# CN-Cape003_ohne_HDMI.net
KiCad netlist of a schematic drawn in EAGLE
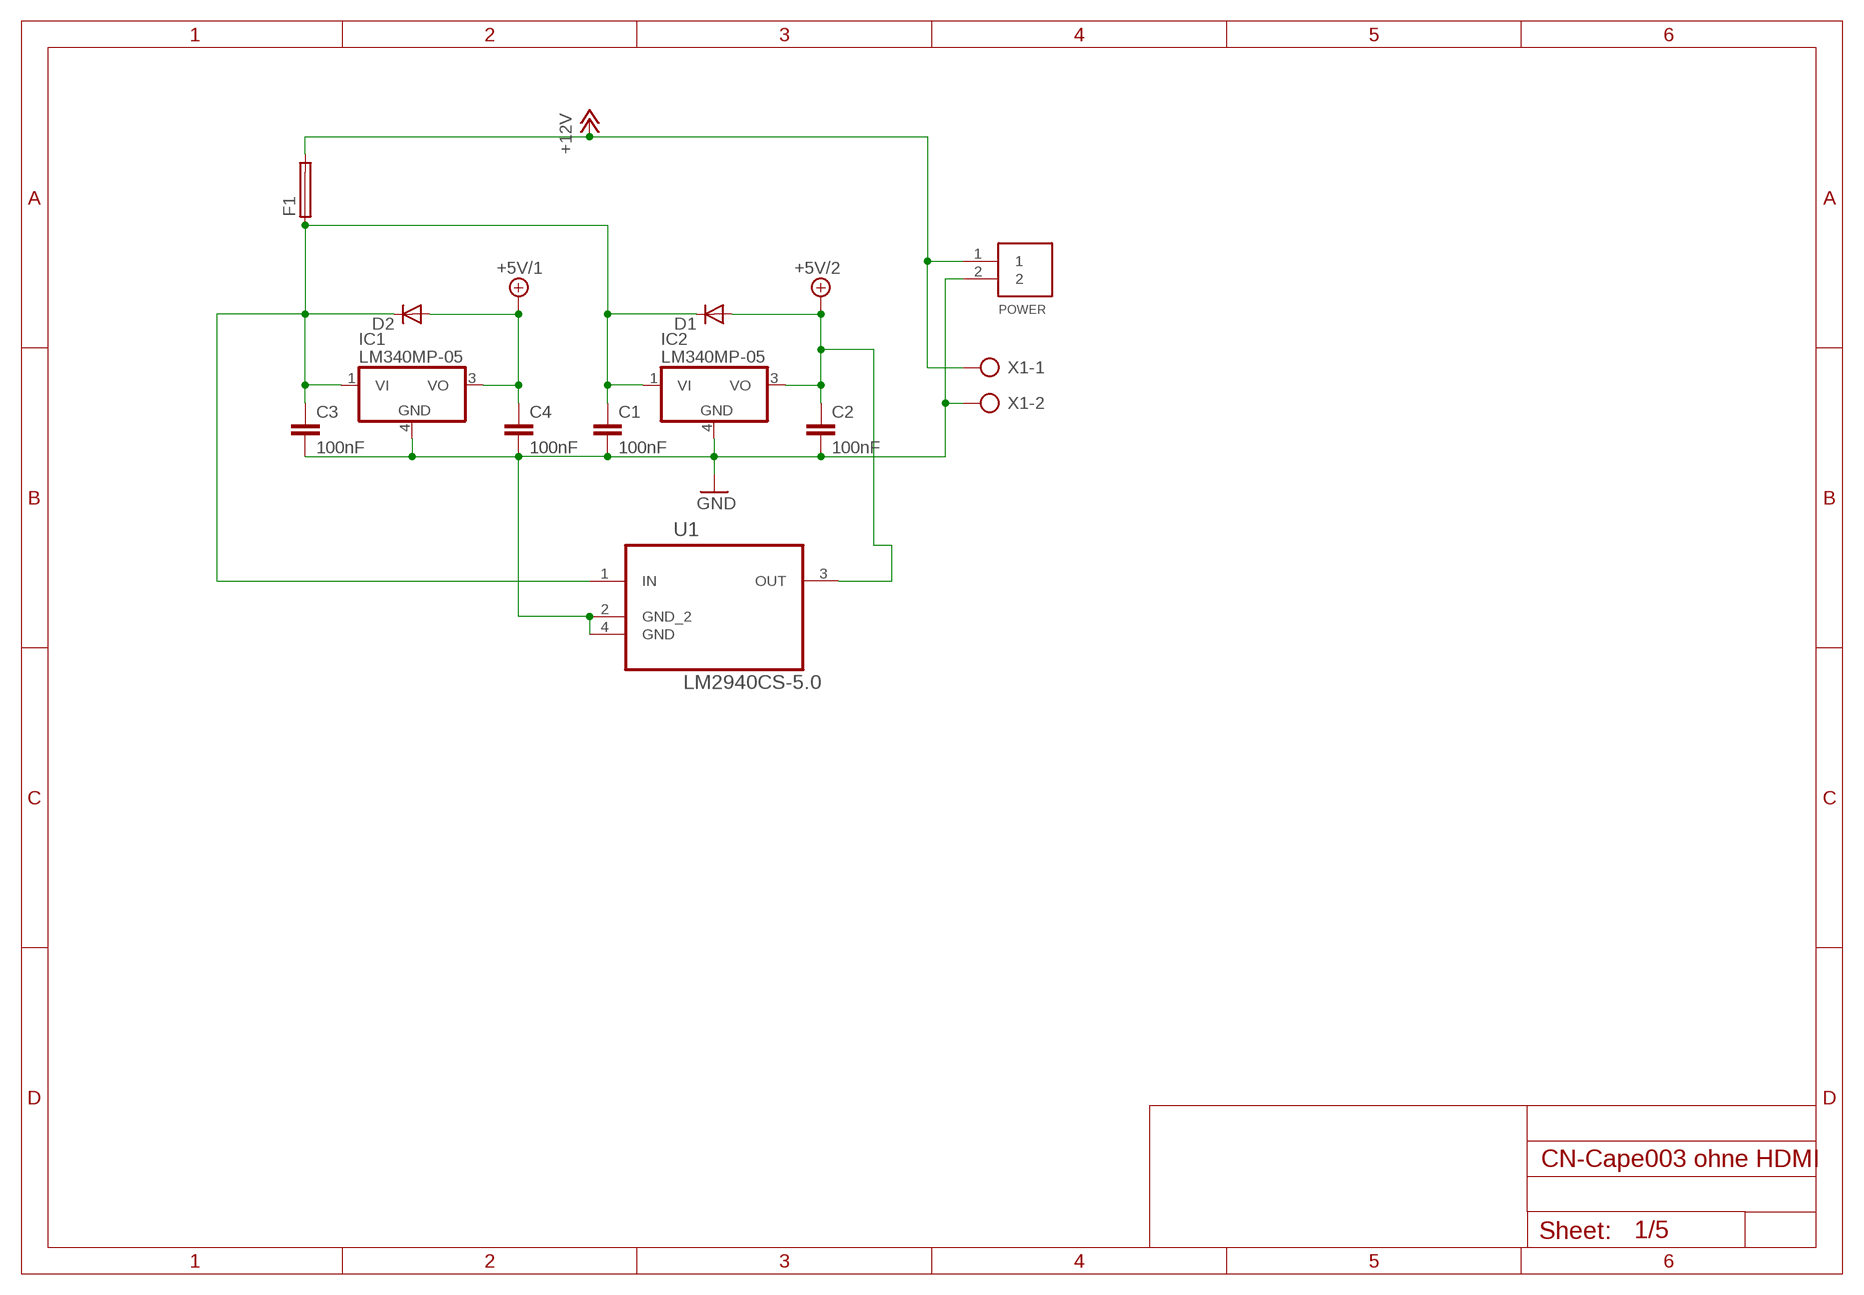
[diagram p0: schematic, sheet 1]
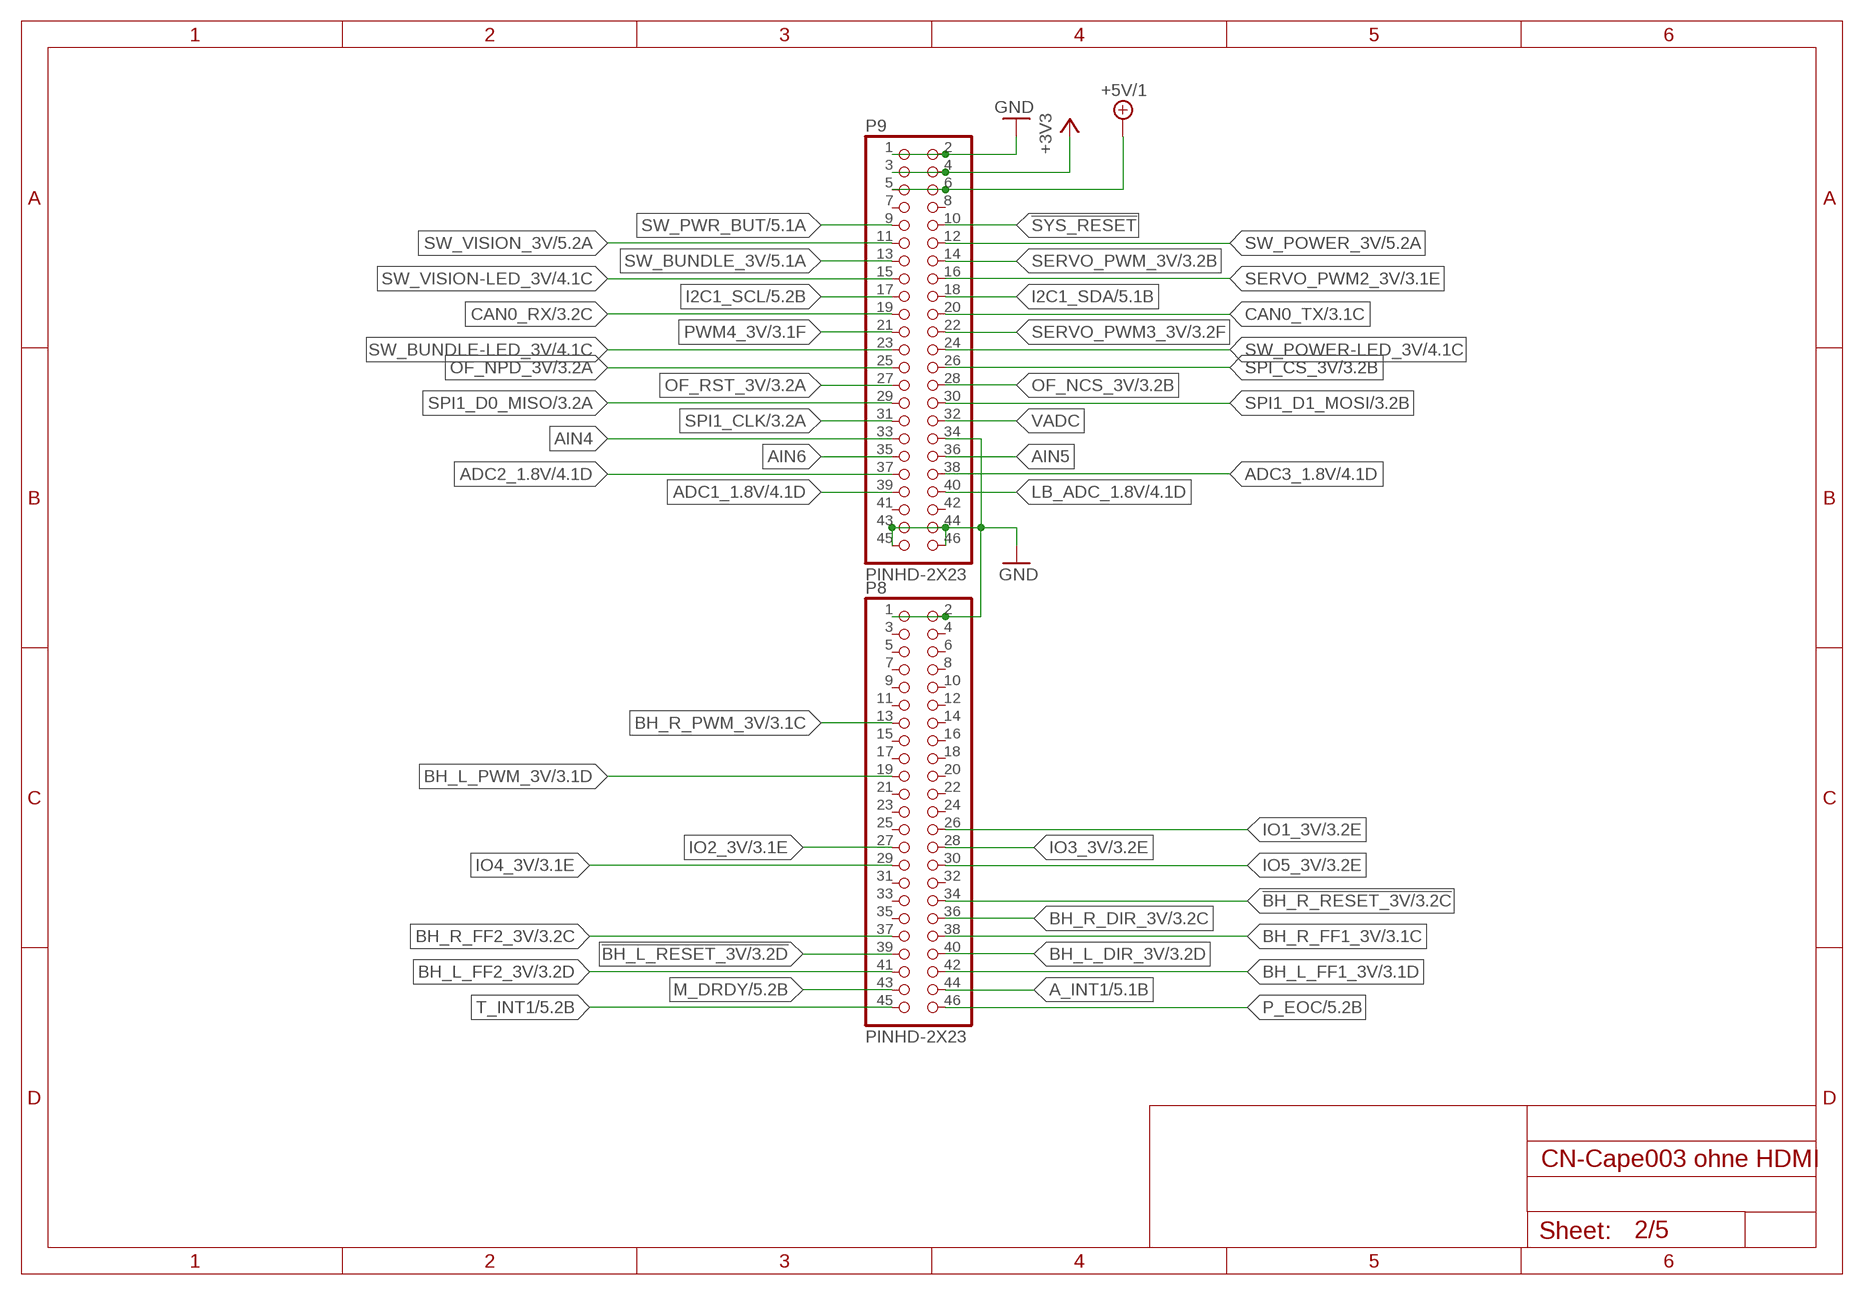
[diagram p1: schematic, sheet 2]
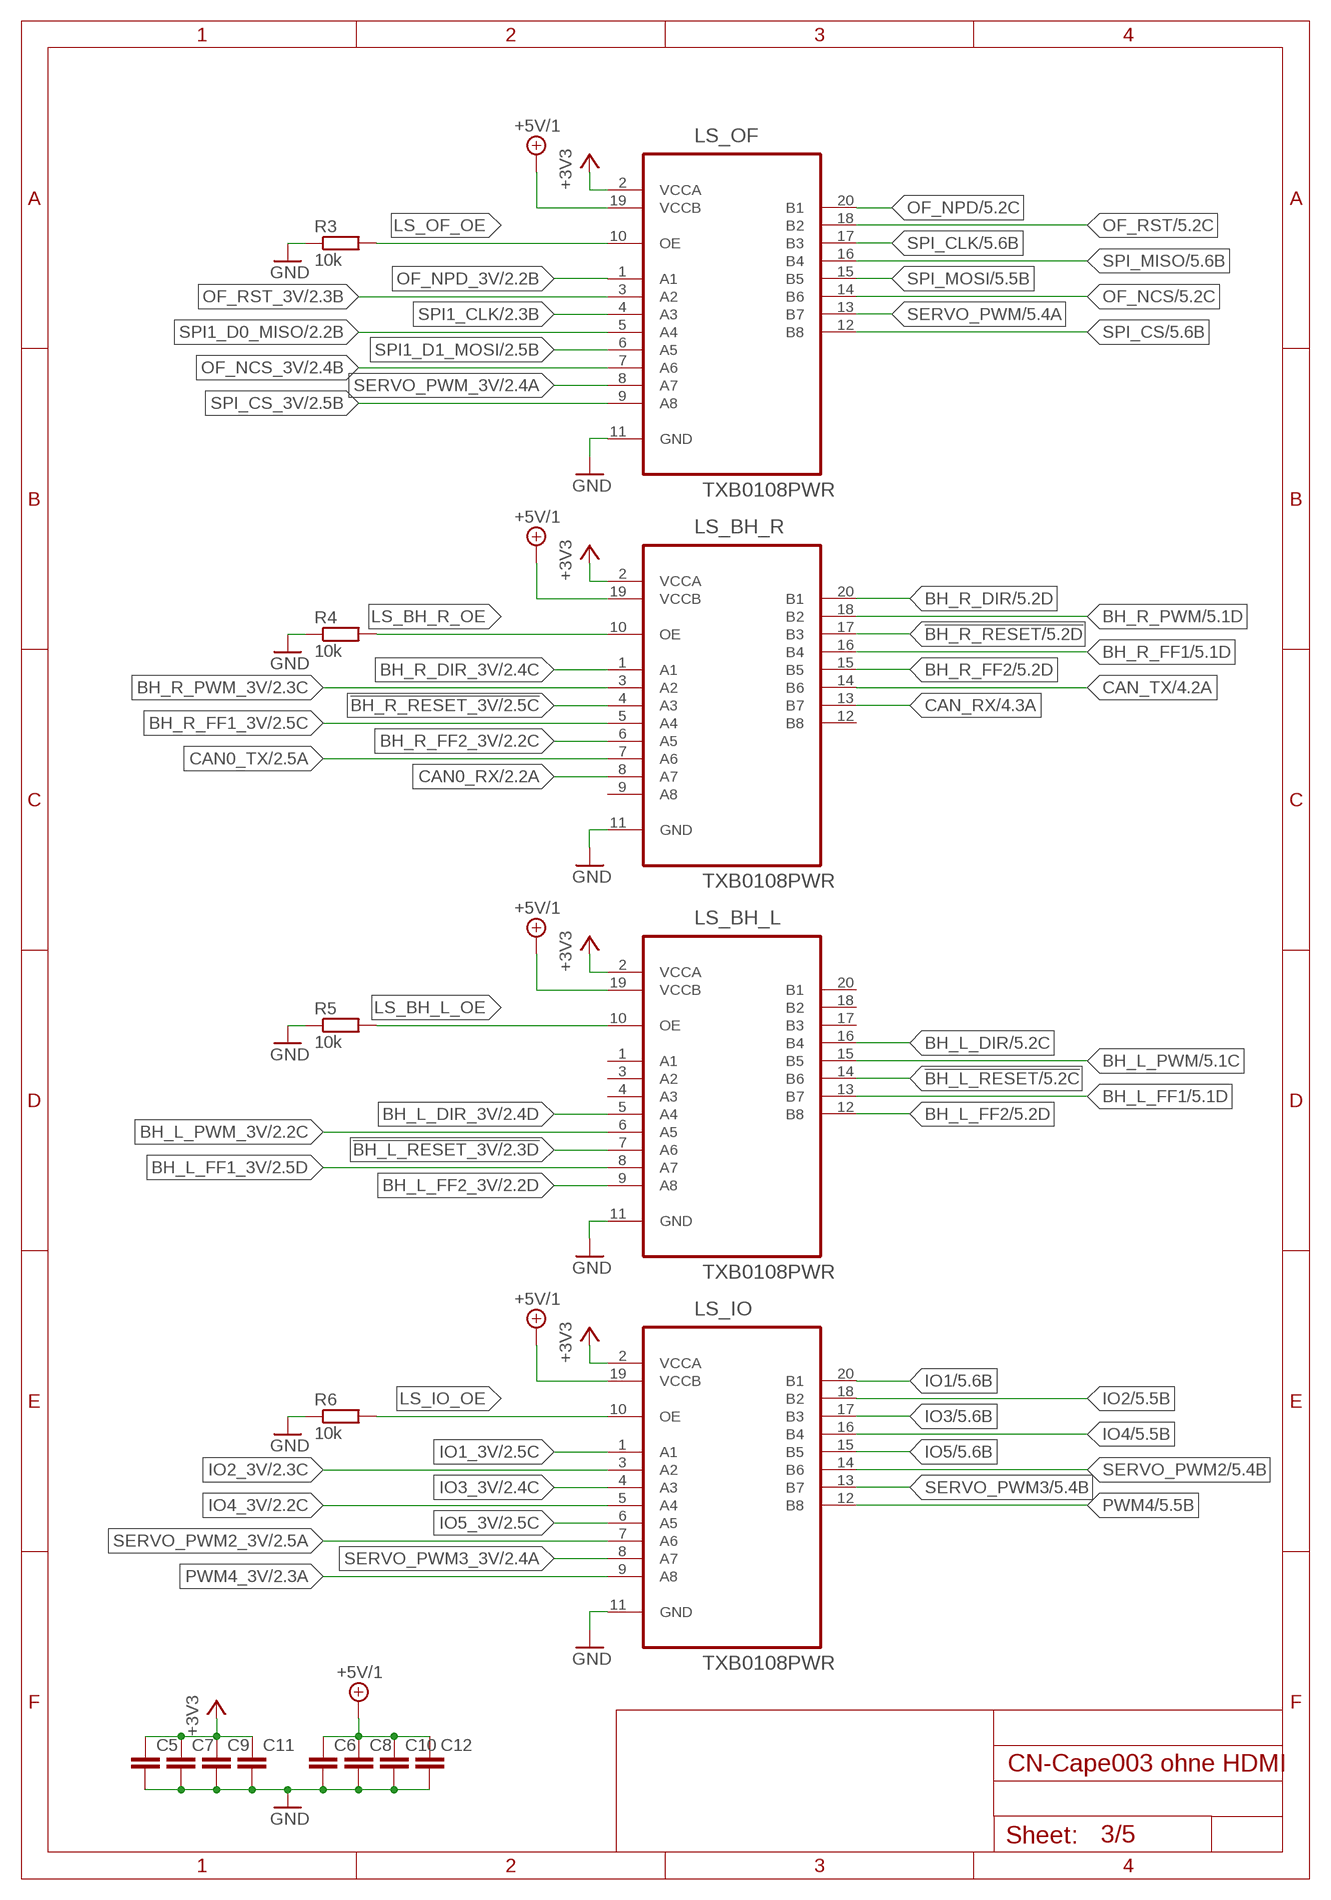
[diagram p2: schematic, sheet 3]
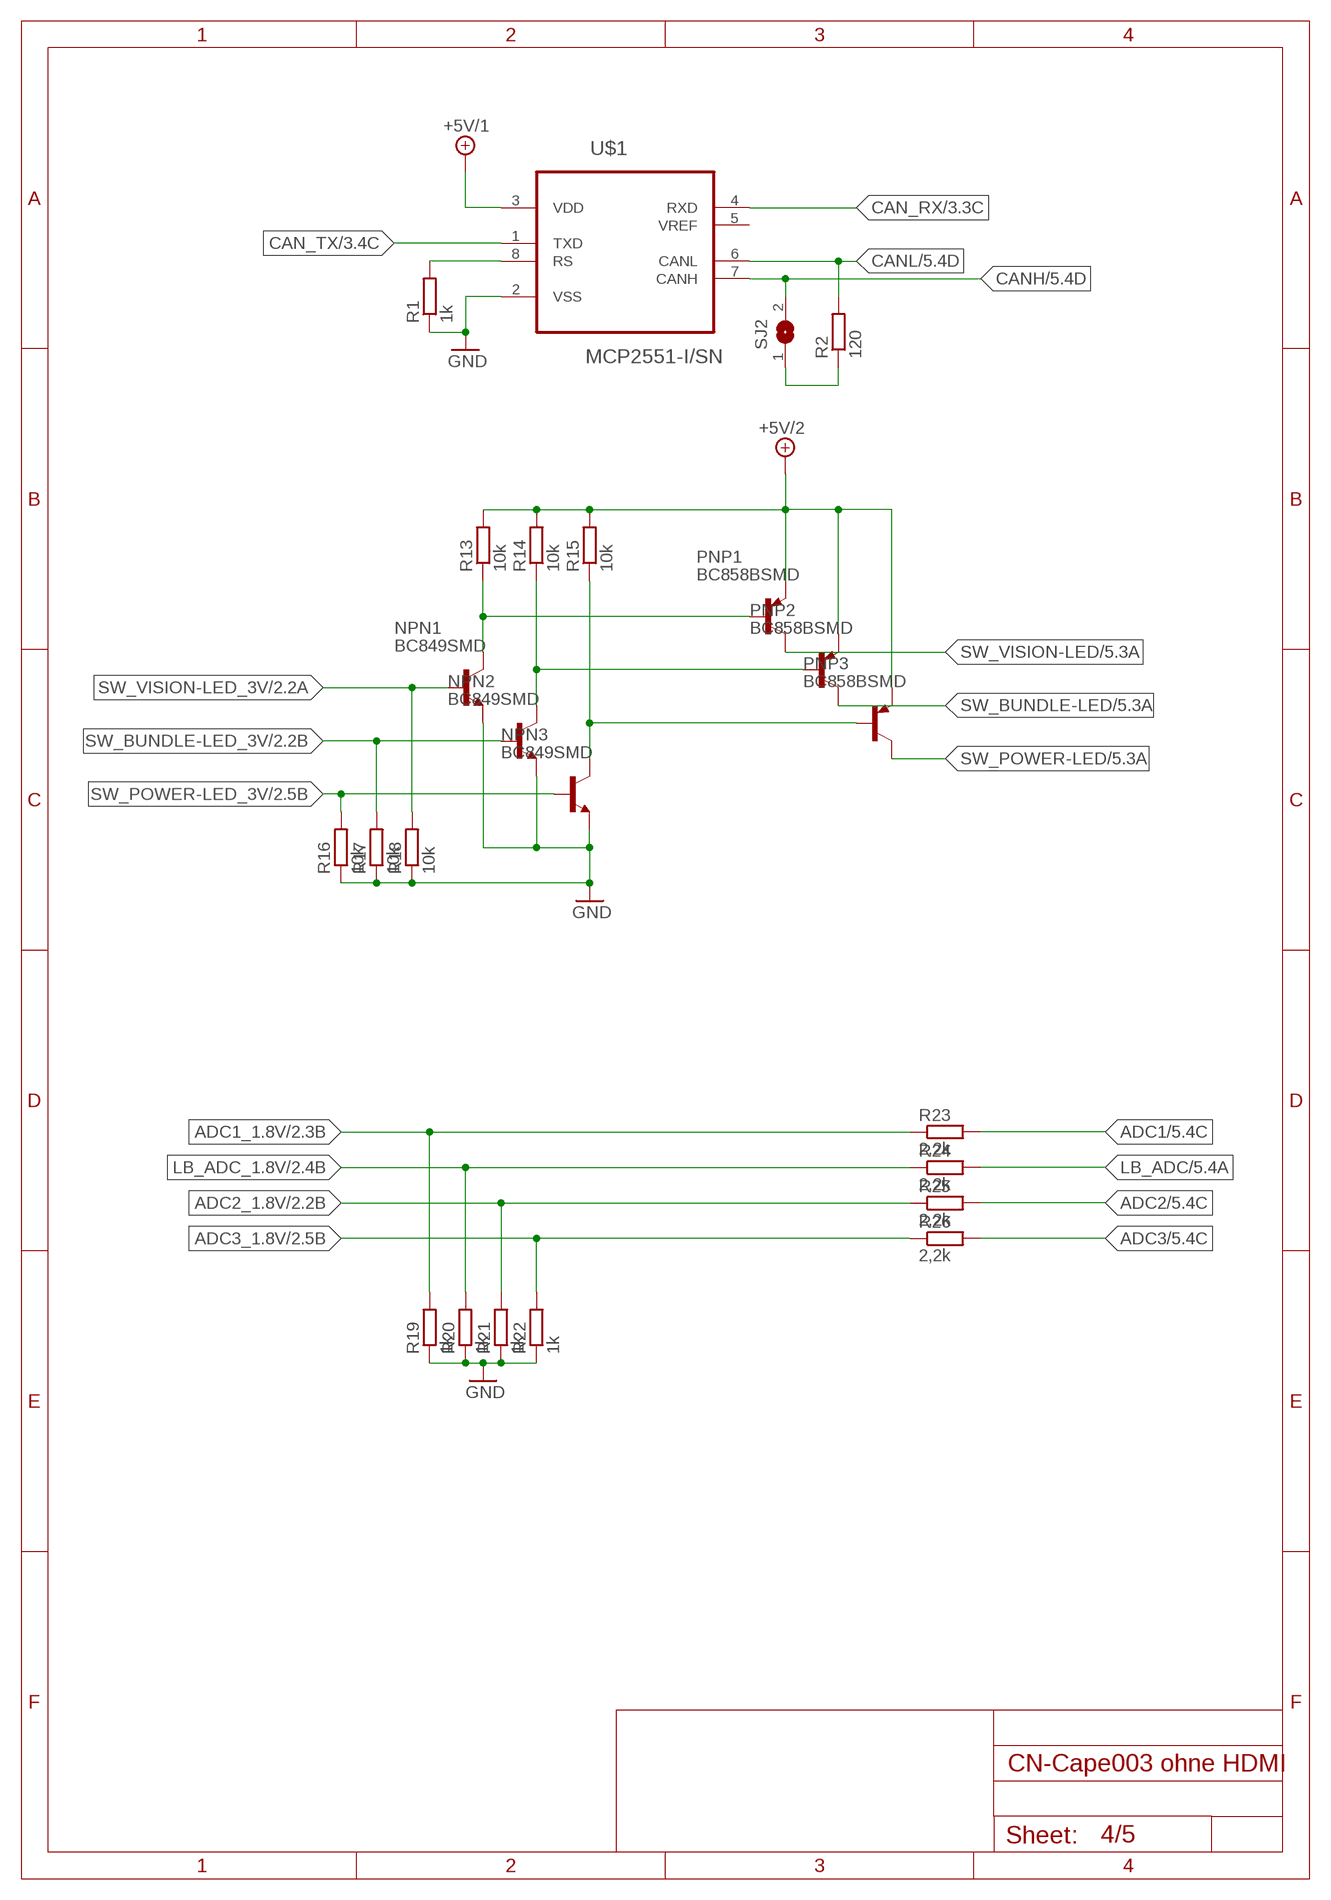
[diagram p3: schematic, sheet 4]
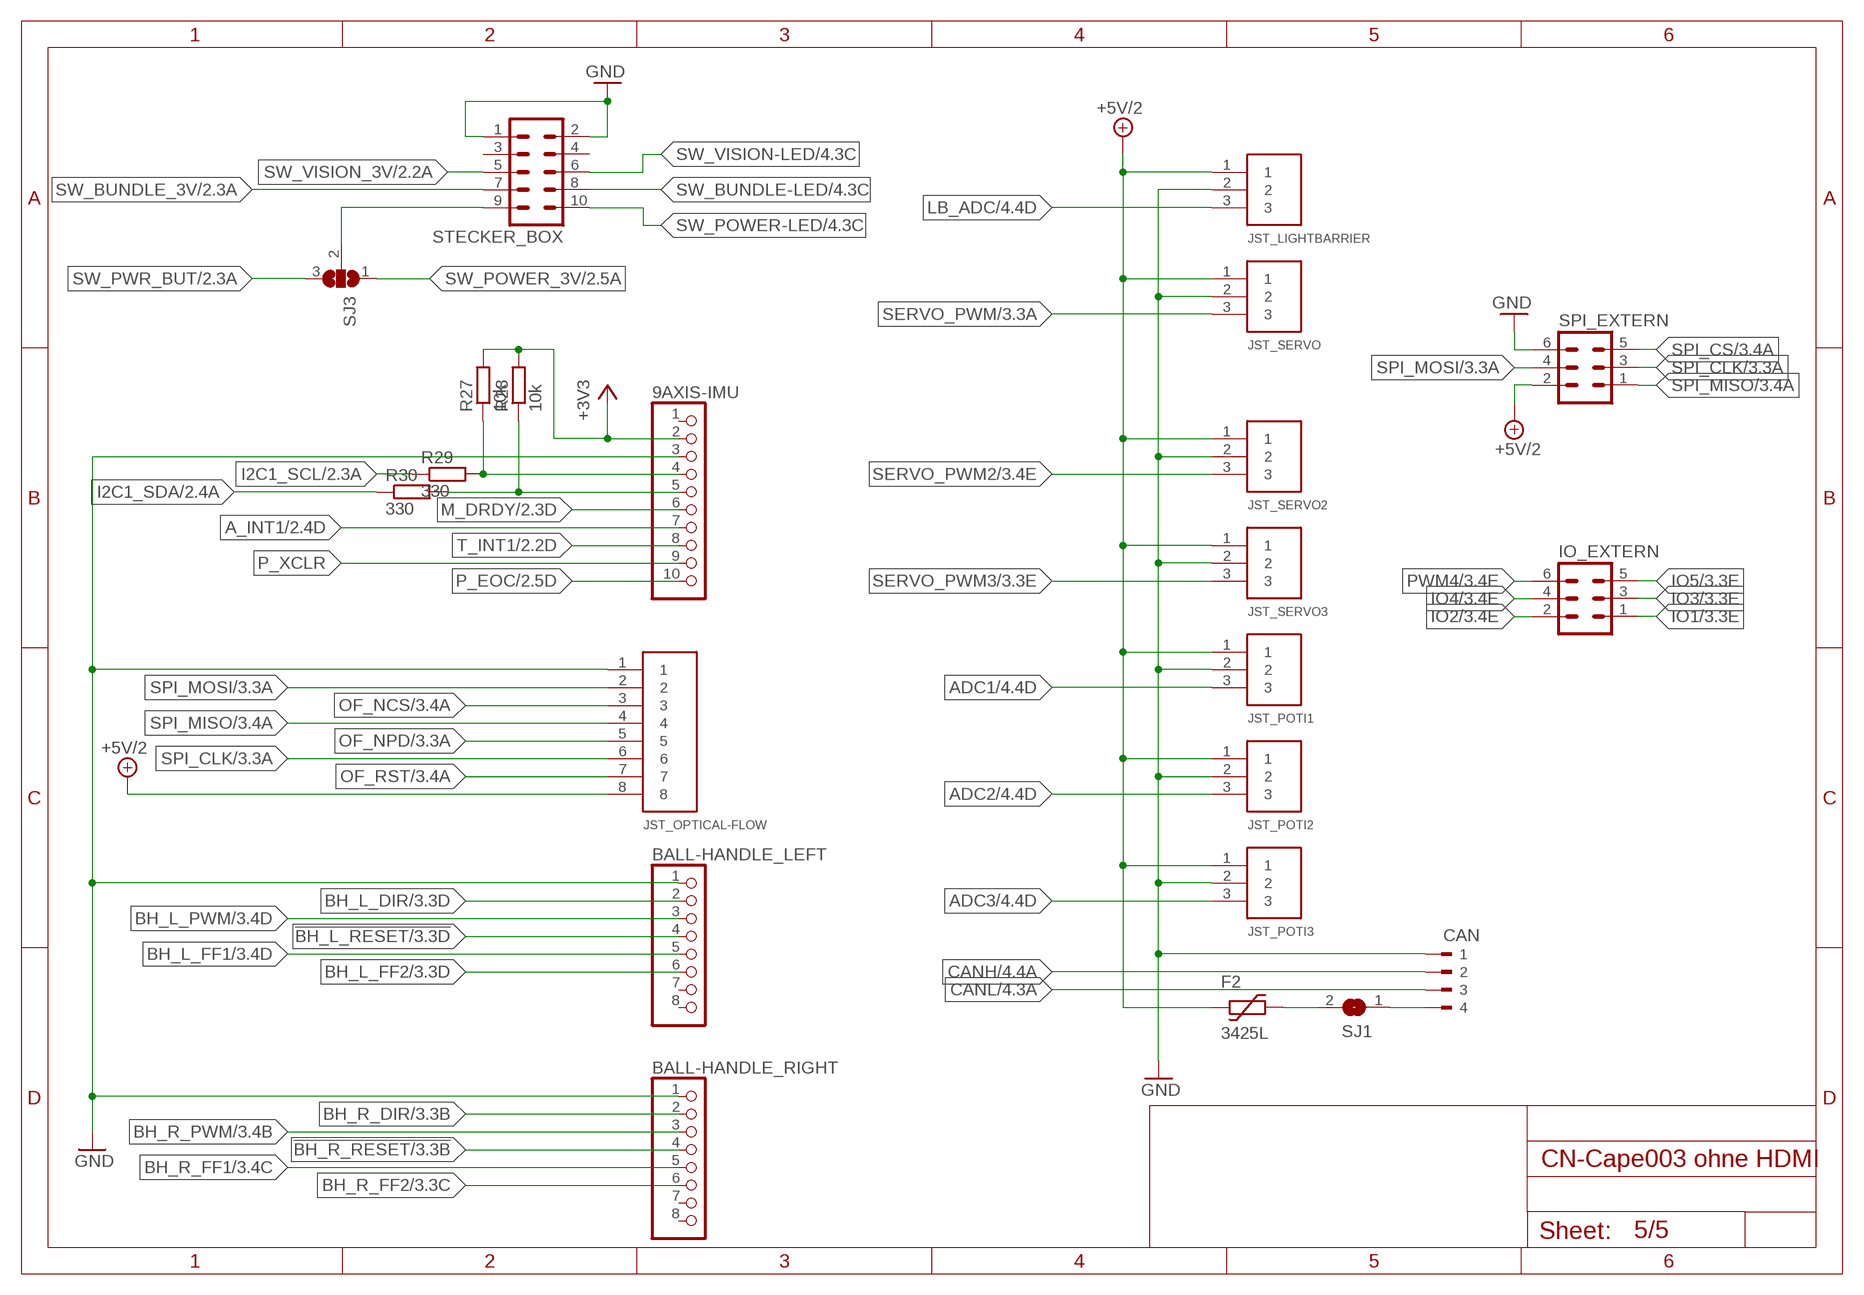
[diagram p4: schematic, sheet 5]

(export (version "E")
  (design (tool "Eeschema 10.0.6"))
  (components
    (comp (ref "C1")
      (value "100nF")
      (footprint "eagle-import:C0805")
      (libsource (lib "eagle-import") (part "C-EUC0805"))
    )
    (comp (ref "C2")
      (value "100nF")
      (footprint "eagle-import:C0805")
      (libsource (lib "eagle-import") (part "C-EUC0805"))
    )
    (comp (ref "C3")
      (value "100nF")
      (footprint "eagle-import:C0805")
      (libsource (lib "eagle-import") (part "C-EUC0805"))
    )
    (comp (ref "C4")
      (value "100nF")
      (footprint "eagle-import:C0805")
      (libsource (lib "eagle-import") (part "C-EUC0805"))
    )
    (comp (ref "D1")
      (value "DIODE-SOD123")
      (footprint "eagle-import:SOD123")
      (libsource (lib "eagle-import") (part "DIODE-SOD123"))
    )
    (comp (ref "D2")
      (value "DIODE-SOD123")
      (footprint "eagle-import:SOD123")
      (libsource (lib "eagle-import") (part "DIODE-SOD123"))
    )
    (comp (ref "F1")
      (value "SH22,5")
      (footprint "eagle-import:SH22,5")
      (libsource (lib "eagle-import") (part "SH22,5"))
    )
    (comp (ref "IC1")
      (value "LM340MP-05")
      (footprint "eagle-import:SOT223")
      (libsource (lib "eagle-import") (part "LM340?-MP05"))
    )
    (comp (ref "IC2")
      (value "LM340MP-05")
      (footprint "eagle-import:SOT223")
      (libsource (lib "eagle-import") (part "LM340?-MP05"))
    )
    (comp (ref "POWER")
      (value "S2PIN")
      (footprint "eagle-import:S2B-EH")
      (libsource (lib "eagle-import") (part "S2PIN"))
    )
    (comp (ref "U1")
      (value "LM2940CS-5.0")
      (footprint "eagle-import:TO254P1435X464-4N")
      (libsource (lib "eagle-import") (part "LM2940CS-5.0"))
    )
    (comp (ref "X1")
      (value "AK500/2-H")
      (footprint "eagle-import:AK500_2-H")
      (libsource (lib "eagle-import") (part "AK500/2-H"))
    )
    (comp (ref "NPN1")
      (value "BC849SMD")
      (footprint "eagle-import:SOT23-BEC")
      (libsource (lib "eagle-import") (part "BC849SMD"))
    )
    (comp (ref "NPN2")
      (value "BC849SMD")
      (footprint "eagle-import:SOT23-BEC")
      (libsource (lib "eagle-import") (part "BC849SMD"))
    )
    (comp (ref "NPN3")
      (value "BC849SMD")
      (footprint "eagle-import:SOT23-BEC")
      (libsource (lib "eagle-import") (part "BC849SMD"))
    )
    (comp (ref "PNP1")
      (value "BC858BSMD")
      (footprint "eagle-import:SOT23-BEC")
      (libsource (lib "eagle-import") (part "BC858SMDB"))
    )
    (comp (ref "PNP2")
      (value "BC858BSMD")
      (footprint "eagle-import:SOT23-BEC")
      (libsource (lib "eagle-import") (part "BC858SMDB"))
    )
    (comp (ref "PNP3")
      (value "BC858BSMD")
      (footprint "eagle-import:SOT23-BEC")
      (libsource (lib "eagle-import") (part "BC858SMDB"))
    )
    (comp (ref "R1")
      (value "1k")
      (footprint "eagle-import:R0603")
      (libsource (lib "eagle-import") (part "R-EU_R0603"))
    )
    (comp (ref "R2")
      (value "120")
      (footprint "eagle-import:R0603")
      (libsource (lib "eagle-import") (part "R-EU_R0603"))
    )
    (comp (ref "R13")
      (value "10k")
      (footprint "eagle-import:R0603")
      (libsource (lib "eagle-import") (part "R-EU_R0603"))
    )
    (comp (ref "R14")
      (value "10k")
      (footprint "eagle-import:R0603")
      (libsource (lib "eagle-import") (part "R-EU_R0603"))
    )
    (comp (ref "R15")
      (value "10k")
      (footprint "eagle-import:R0603")
      (libsource (lib "eagle-import") (part "R-EU_R0603"))
    )
    (comp (ref "R16")
      (value "10k")
      (footprint "eagle-import:R0603")
      (libsource (lib "eagle-import") (part "R-EU_R0603"))
    )
    (comp (ref "R17")
      (value "10k")
      (footprint "eagle-import:R0603")
      (libsource (lib "eagle-import") (part "R-EU_R0603"))
    )
    (comp (ref "R18")
      (value "10k")
      (footprint "eagle-import:R0603")
      (libsource (lib "eagle-import") (part "R-EU_R0603"))
    )
    (comp (ref "R19")
      (value "1k")
      (footprint "eagle-import:R0603")
      (libsource (lib "eagle-import") (part "R-EU_R0603"))
    )
    (comp (ref "R20")
      (value "1k")
      (footprint "eagle-import:R0603")
      (libsource (lib "eagle-import") (part "R-EU_R0603"))
    )
    (comp (ref "R21")
      (value "1k")
      (footprint "eagle-import:R0603")
      (libsource (lib "eagle-import") (part "R-EU_R0603"))
    )
    (comp (ref "R22")
      (value "1k")
      (footprint "eagle-import:R0603")
      (libsource (lib "eagle-import") (part "R-EU_R0603"))
    )
    (comp (ref "R23")
      (value "2,2k")
      (footprint "eagle-import:R0603")
      (libsource (lib "eagle-import") (part "R-EU_R0603"))
    )
    (comp (ref "R24")
      (value "2,2k")
      (footprint "eagle-import:R0603")
      (libsource (lib "eagle-import") (part "R-EU_R0603"))
    )
    (comp (ref "R25")
      (value "2,2k")
      (footprint "eagle-import:R0603")
      (libsource (lib "eagle-import") (part "R-EU_R0603"))
    )
    (comp (ref "R26")
      (value "2,2k")
      (footprint "eagle-import:R0603")
      (libsource (lib "eagle-import") (part "R-EU_R0603"))
    )
    (comp (ref "SJ2") (value "SJ") (footprint "eagle-import:SJ") (libsource (lib "eagle-import") (part "SJ")))
    (comp (ref "U$1")
      (value "MCP2551-I/SN")
      (footprint "eagle-import:SOIC127P600X175-8N")
      (libsource (lib "eagle-import") (part "MCP2551-I/SN"))
    )
    (comp (ref "C5")
      (value "C-EUC0805")
      (footprint "eagle-import:C0805")
      (libsource (lib "eagle-import") (part "C-EUC0805"))
    )
    (comp (ref "C6")
      (value "C-EUC0805")
      (footprint "eagle-import:C0805")
      (libsource (lib "eagle-import") (part "C-EUC0805"))
    )
    (comp (ref "C7")
      (value "C-EUC0805")
      (footprint "eagle-import:C0805")
      (libsource (lib "eagle-import") (part "C-EUC0805"))
    )
    (comp (ref "C8")
      (value "C-EUC0805")
      (footprint "eagle-import:C0805")
      (libsource (lib "eagle-import") (part "C-EUC0805"))
    )
    (comp (ref "C9")
      (value "C-EUC0805")
      (footprint "eagle-import:C0805")
      (libsource (lib "eagle-import") (part "C-EUC0805"))
    )
    (comp (ref "C10")
      (value "C-EUC0805")
      (footprint "eagle-import:C0805")
      (libsource (lib "eagle-import") (part "C-EUC0805"))
    )
    (comp (ref "C11")
      (value "C-EUC0805")
      (footprint "eagle-import:C0805")
      (libsource (lib "eagle-import") (part "C-EUC0805"))
    )
    (comp (ref "C12")
      (value "C-EUC0805")
      (footprint "eagle-import:C0805")
      (libsource (lib "eagle-import") (part "C-EUC0805"))
    )
    (comp (ref "LS_BH_L")
      (value "TXB0108PWR")
      (footprint "eagle-import:SOP65P640X120-20N")
      (libsource (lib "eagle-import") (part "TXB0108PWR"))
    )
    (comp (ref "LS_BH_R")
      (value "TXB0108PWR")
      (footprint "eagle-import:SOP65P640X120-20N")
      (libsource (lib "eagle-import") (part "TXB0108PWR"))
    )
    (comp (ref "LS_IO")
      (value "TXB0108PWR")
      (footprint "eagle-import:SOP65P640X120-20N")
      (libsource (lib "eagle-import") (part "TXB0108PWR"))
    )
    (comp (ref "LS_OF")
      (value "TXB0108PWR")
      (footprint "eagle-import:SOP65P640X120-20N")
      (libsource (lib "eagle-import") (part "TXB0108PWR"))
    )
    (comp (ref "R3")
      (value "10k")
      (footprint "eagle-import:R0603")
      (libsource (lib "eagle-import") (part "R-EU_R0603"))
    )
    (comp (ref "R4")
      (value "10k")
      (footprint "eagle-import:R0603")
      (libsource (lib "eagle-import") (part "R-EU_R0603"))
    )
    (comp (ref "R5")
      (value "10k")
      (footprint "eagle-import:R0603")
      (libsource (lib "eagle-import") (part "R-EU_R0603"))
    )
    (comp (ref "R6")
      (value "10k")
      (footprint "eagle-import:R0603")
      (libsource (lib "eagle-import") (part "R-EU_R0603"))
    )
    (comp (ref "P8")
      (value "PINHD-2X23")
      (footprint "eagle-import:2X23")
      (libsource (lib "eagle-import") (part "PINHD-2X23"))
    )
    (comp (ref "P9")
      (value "PINHD-2X23")
      (footprint "eagle-import:2X23")
      (libsource (lib "eagle-import") (part "PINHD-2X23"))
    )
    (comp (ref "9AXIS-IMU")
      (value "PINHD-1X10")
      (footprint "eagle-import:1X10")
      (libsource (lib "eagle-import") (part "PINHD-1X10"))
    )
    (comp (ref "BALL-HANDLE_LEFT")
      (value "PINHD-1X8")
      (footprint "eagle-import:1X08")
      (libsource (lib "eagle-import") (part "PINHD-1X8"))
    )
    (comp (ref "BALL-HANDLE_RIGHT")
      (value "PINHD-1X8")
      (footprint "eagle-import:1X08")
      (libsource (lib "eagle-import") (part "PINHD-1X8"))
    )
    (comp (ref "CAN")
      (value "90-4")
      (footprint "eagle-import:90-4")
      (libsource (lib "eagle-import") (part "90-4"))
    )
    (comp (ref "F2")
      (value "3425L")
      (footprint "eagle-import:3425L")
      (libsource (lib "eagle-import") (part "3425L"))
    )
    (comp (ref "IO_EXTERN")
      (value "ML6")
      (footprint "eagle-import:ML6")
      (libsource (lib "eagle-import") (part "ML6"))
    )
    (comp (ref "JST_LIGHTBARRIER")
      (value "S3PIN")
      (footprint "eagle-import:S3B-EH")
      (libsource (lib "eagle-import") (part "S3PIN"))
    )
    (comp (ref "JST_OPTICAL-FLOW")
      (value "S8PIN")
      (footprint "eagle-import:S8B-EH")
      (libsource (lib "eagle-import") (part "S8PIN"))
    )
    (comp (ref "JST_POTI1")
      (value "3PIN")
      (footprint "eagle-import:B3B-EH")
      (libsource (lib "eagle-import") (part "3PIN"))
    )
    (comp (ref "JST_POTI2")
      (value "3PIN")
      (footprint "eagle-import:B3B-EH")
      (libsource (lib "eagle-import") (part "3PIN"))
    )
    (comp (ref "JST_POTI3")
      (value "3PIN")
      (footprint "eagle-import:B3B-EH")
      (libsource (lib "eagle-import") (part "3PIN"))
    )
    (comp (ref "JST_SERVO")
      (value "S3PIN")
      (footprint "eagle-import:S3B-EH")
      (libsource (lib "eagle-import") (part "S3PIN"))
    )
    (comp (ref "JST_SERVO2")
      (value "3PIN")
      (footprint "eagle-import:B3B-EH")
      (libsource (lib "eagle-import") (part "3PIN"))
    )
    (comp (ref "JST_SERVO3")
      (value "3PIN")
      (footprint "eagle-import:B3B-EH")
      (libsource (lib "eagle-import") (part "3PIN"))
    )
    (comp (ref "R27")
      (value "10k")
      (footprint "eagle-import:R0603")
      (libsource (lib "eagle-import") (part "R-EU_R0603"))
    )
    (comp (ref "R28")
      (value "10k")
      (footprint "eagle-import:R0603")
      (libsource (lib "eagle-import") (part "R-EU_R0603"))
    )
    (comp (ref "R29")
      (value "330")
      (footprint "eagle-import:R0603")
      (libsource (lib "eagle-import") (part "R-EU_R0603"))
    )
    (comp (ref "R30")
      (value "330")
      (footprint "eagle-import:R0603")
      (libsource (lib "eagle-import") (part "R-EU_R0603"))
    )
    (comp (ref "SJ1") (value "SJ") (footprint "eagle-import:SJ") (libsource (lib "eagle-import") (part "SJ")))
    (comp (ref "SJ3")
      (value "SJ2W")
      (footprint "eagle-import:SJ_2")
      (libsource (lib "eagle-import") (part "SJ2W"))
    )
    (comp (ref "SPI_EXTERN")
      (value "ML6")
      (footprint "eagle-import:ML6")
      (libsource (lib "eagle-import") (part "ML6"))
    )
    (comp (ref "STECKER_BOX")
      (value "ML10")
      (footprint "eagle-import:ML10")
      (libsource (lib "eagle-import") (part "ML10"))
    )
  )
  (nets
    (net (code "1") (name "+3V3") (class "Default")
      (node (ref "9AXIS-IMU") (pin "2") (pinfunction "2_2") (pintype "passive"))
      (node (ref "C11") (pin "1") (pinfunction "1_1") (pintype "passive"))
      (node (ref "C5") (pin "1") (pinfunction "1_1") (pintype "passive"))
      (node (ref "C7") (pin "1") (pinfunction "1_1") (pintype "passive"))
      (node (ref "C9") (pin "1") (pinfunction "1_1") (pintype "passive"))
      (node (ref "LS_BH_L") (pin "2") (pinfunction "VCCA_2") (pintype "power_in"))
      (node (ref "LS_BH_R") (pin "2") (pinfunction "VCCA_2") (pintype "power_in"))
      (node (ref "LS_IO") (pin "2") (pinfunction "VCCA_2") (pintype "power_in"))
      (node (ref "LS_OF") (pin "2") (pinfunction "VCCA_2") (pintype "power_in"))
      (node (ref "P9") (pin "3") (pinfunction "3_3") (pintype "passive"))
      (node (ref "P9") (pin "4") (pinfunction "4_4") (pintype "passive"))
      (node (ref "R27") (pin "2") (pinfunction "2_2") (pintype "passive"))
      (node (ref "R28") (pin "2") (pinfunction "2_2") (pintype "passive"))
    )
    (net (code "2") (name "+5V{slash}1") (class "Default")
      (node (ref "C10") (pin "1") (pinfunction "1_1") (pintype "passive"))
      (node (ref "C12") (pin "1") (pinfunction "1_1") (pintype "passive"))
      (node (ref "C4") (pin "1") (pinfunction "1_1") (pintype "passive"))
      (node (ref "C6") (pin "1") (pinfunction "1_1") (pintype "passive"))
      (node (ref "C8") (pin "1") (pinfunction "1_1") (pintype "passive"))
      (node (ref "D2") (pin "A") (pinfunction "A_A") (pintype "passive"))
      (node (ref "IC1") (pin "3") (pinfunction "VO_3") (pintype "passive"))
      (node (ref "LS_BH_L") (pin "19") (pinfunction "VCCB_19") (pintype "power_in"))
      (node (ref "LS_BH_R") (pin "19") (pinfunction "VCCB_19") (pintype "power_in"))
      (node (ref "LS_IO") (pin "19") (pinfunction "VCCB_19") (pintype "power_in"))
      (node (ref "LS_OF") (pin "19") (pinfunction "VCCB_19") (pintype "power_in"))
      (node (ref "P9") (pin "5") (pinfunction "5_5") (pintype "passive"))
      (node (ref "P9") (pin "6") (pinfunction "6_6") (pintype "passive"))
      (node (ref "U$1") (pin "3") (pinfunction "VDD_3") (pintype "power_in"))
    )
    (net (code "3") (name "+5V{slash}2") (class "Default")
      (node (ref "C2") (pin "1") (pinfunction "1_1") (pintype "passive"))
      (node (ref "D1") (pin "A") (pinfunction "A_A") (pintype "passive"))
      (node (ref "F2") (pin "P$1") (pinfunction "1_P$1") (pintype "passive"))
      (node (ref "IC2") (pin "3") (pinfunction "VO_3") (pintype "passive"))
      (node (ref "JST_LIGHTBARRIER") (pin "1") (pinfunction "1_1") (pintype "bidirectional"))
      (node (ref "JST_OPTICAL-FLOW") (pin "8") (pinfunction "8_8") (pintype "bidirectional"))
      (node (ref "JST_POTI1") (pin "1") (pinfunction "1_1") (pintype "bidirectional"))
      (node (ref "JST_POTI2") (pin "1") (pinfunction "1_1") (pintype "bidirectional"))
      (node (ref "JST_POTI3") (pin "1") (pinfunction "1_1") (pintype "bidirectional"))
      (node (ref "JST_SERVO") (pin "1") (pinfunction "1_1") (pintype "bidirectional"))
      (node (ref "JST_SERVO2") (pin "1") (pinfunction "1_1") (pintype "bidirectional"))
      (node (ref "JST_SERVO3") (pin "1") (pinfunction "1_1") (pintype "bidirectional"))
      (node (ref "PNP1") (pin "E") (pinfunction "E_E") (pintype "passive"))
      (node (ref "PNP2") (pin "E") (pinfunction "E_E") (pintype "passive"))
      (node (ref "PNP3") (pin "E") (pinfunction "E_E") (pintype "passive"))
      (node (ref "R13") (pin "2") (pinfunction "2_2") (pintype "passive"))
      (node (ref "R14") (pin "2") (pinfunction "2_2") (pintype "passive"))
      (node (ref "R15") (pin "2") (pinfunction "2_2") (pintype "passive"))
      (node (ref "SPI_EXTERN") (pin "2") (pinfunction "2_2") (pintype "passive"))
      (node (ref "U1") (pin "3") (pinfunction "OUT_3") (pintype "output"))
    )
    (net (code "4") (name "+12V") (class "Default")
      (node (ref "F1") (pin "2") (pinfunction "2_2") (pintype "passive"))
      (node (ref "POWER") (pin "1") (pinfunction "1_1") (pintype "bidirectional"))
      (node (ref "X1") (pin "1") (pinfunction "KL_1") (pintype "passive"))
    )
    (net (code "5") (name "ADC1") (class "Default")
      (node (ref "JST_POTI1") (pin "3") (pinfunction "3_3") (pintype "bidirectional"))
      (node (ref "R23") (pin "2") (pinfunction "2_2") (pintype "passive"))
    )
    (net (code "6") (name "ADC1_1.8V") (class "Default")
      (node (ref "P9") (pin "39") (pinfunction "39_39") (pintype "passive"))
      (node (ref "R19") (pin "2") (pinfunction "2_2") (pintype "passive"))
      (node (ref "R23") (pin "1") (pinfunction "1_1") (pintype "passive"))
    )
    (net (code "7") (name "ADC2") (class "Default")
      (node (ref "JST_POTI2") (pin "3") (pinfunction "3_3") (pintype "bidirectional"))
      (node (ref "R25") (pin "2") (pinfunction "2_2") (pintype "passive"))
    )
    (net (code "8") (name "ADC2_1.8V") (class "Default")
      (node (ref "P9") (pin "37") (pinfunction "37_37") (pintype "passive"))
      (node (ref "R21") (pin "2") (pinfunction "2_2") (pintype "passive"))
      (node (ref "R25") (pin "1") (pinfunction "1_1") (pintype "passive"))
    )
    (net (code "9") (name "ADC3") (class "Default")
      (node (ref "JST_POTI3") (pin "3") (pinfunction "3_3") (pintype "bidirectional"))
      (node (ref "R26") (pin "2") (pinfunction "2_2") (pintype "passive"))
    )
    (net (code "10") (name "ADC3_1.8V") (class "Default")
      (node (ref "P9") (pin "38") (pinfunction "38_38") (pintype "passive"))
      (node (ref "R22") (pin "2") (pinfunction "2_2") (pintype "passive"))
      (node (ref "R26") (pin "1") (pinfunction "1_1") (pintype "passive"))
    )
    (net (code "11") (name "AIN4") (class "Default")
      (node (ref "P9") (pin "33") (pinfunction "33_33") (pintype "passive"))
    )
    (net (code "12") (name "AIN5") (class "Default")
      (node (ref "P9") (pin "36") (pinfunction "36_36") (pintype "passive"))
    )
    (net (code "13") (name "AIN6") (class "Default")
      (node (ref "P9") (pin "35") (pinfunction "35_35") (pintype "passive"))
    )
    (net (code "14") (name "A_INT1") (class "Default")
      (node (ref "9AXIS-IMU") (pin "7") (pinfunction "7_7") (pintype "passive"))
      (node (ref "P8") (pin "44") (pinfunction "44_44") (pintype "passive"))
    )
    (net (code "15") (name "BH_L_DIR") (class "Default")
      (node (ref "BALL-HANDLE_LEFT") (pin "2") (pinfunction "2_2") (pintype "passive"))
      (node (ref "LS_BH_L") (pin "16") (pinfunction "B4_16") (pintype "bidirectional"))
    )
    (net (code "16") (name "BH_L_DIR_3V") (class "Default")
      (node (ref "LS_BH_L") (pin "5") (pinfunction "A4_5") (pintype "bidirectional"))
      (node (ref "P8") (pin "40") (pinfunction "40_40") (pintype "passive"))
    )
    (net (code "17") (name "BH_L_FF1") (class "Default")
      (node (ref "BALL-HANDLE_LEFT") (pin "5") (pinfunction "5_5") (pintype "passive"))
      (node (ref "LS_BH_L") (pin "13") (pinfunction "B7_13") (pintype "bidirectional"))
    )
    (net (code "18") (name "BH_L_FF1_3V") (class "Default")
      (node (ref "LS_BH_L") (pin "8") (pinfunction "A7_8") (pintype "bidirectional"))
      (node (ref "P8") (pin "42") (pinfunction "42_42") (pintype "passive"))
    )
    (net (code "19") (name "BH_L_FF2") (class "Default")
      (node (ref "BALL-HANDLE_LEFT") (pin "6") (pinfunction "6_6") (pintype "passive"))
      (node (ref "LS_BH_L") (pin "12") (pinfunction "B8_12") (pintype "bidirectional"))
    )
    (net (code "20") (name "BH_L_FF2_3V") (class "Default")
      (node (ref "LS_BH_L") (pin "9") (pinfunction "A8_9") (pintype "bidirectional"))
      (node (ref "P8") (pin "41") (pinfunction "41_41") (pintype "passive"))
    )
    (net (code "21") (name "BH_L_PWM") (class "Default")
      (node (ref "BALL-HANDLE_LEFT") (pin "3") (pinfunction "3_3") (pintype "passive"))
      (node (ref "LS_BH_L") (pin "15") (pinfunction "B5_15") (pintype "bidirectional"))
    )
    (net (code "22") (name "BH_L_PWM_3V") (class "Default")
      (node (ref "LS_BH_L") (pin "6") (pinfunction "A5_6") (pintype "bidirectional"))
      (node (ref "P8") (pin "19") (pinfunction "19_19") (pintype "passive"))
    )
    (net (code "23") (name "BH_R_DIR") (class "Default")
      (node (ref "BALL-HANDLE_RIGHT") (pin "2") (pinfunction "2_2") (pintype "passive"))
      (node (ref "LS_BH_R") (pin "20") (pinfunction "B1_20") (pintype "bidirectional"))
    )
    (net (code "24") (name "BH_R_DIR_3V") (class "Default")
      (node (ref "LS_BH_R") (pin "1") (pinfunction "A1_1") (pintype "bidirectional"))
      (node (ref "P8") (pin "36") (pinfunction "36_36") (pintype "passive"))
    )
    (net (code "25") (name "BH_R_FF1") (class "Default")
      (node (ref "BALL-HANDLE_RIGHT") (pin "5") (pinfunction "5_5") (pintype "passive"))
      (node (ref "LS_BH_R") (pin "16") (pinfunction "B4_16") (pintype "bidirectional"))
    )
    (net (code "26") (name "BH_R_FF1_3V") (class "Default")
      (node (ref "LS_BH_R") (pin "5") (pinfunction "A4_5") (pintype "bidirectional"))
      (node (ref "P8") (pin "38") (pinfunction "38_38") (pintype "passive"))
    )
    (net (code "27") (name "BH_R_FF2") (class "Default")
      (node (ref "BALL-HANDLE_RIGHT") (pin "6") (pinfunction "6_6") (pintype "passive"))
      (node (ref "LS_BH_R") (pin "15") (pinfunction "B5_15") (pintype "bidirectional"))
    )
    (net (code "28") (name "BH_R_FF2_3V") (class "Default")
      (node (ref "LS_BH_R") (pin "6") (pinfunction "A5_6") (pintype "bidirectional"))
      (node (ref "P8") (pin "37") (pinfunction "37_37") (pintype "passive"))
    )
    (net (code "29") (name "BH_R_PWM") (class "Default")
      (node (ref "BALL-HANDLE_RIGHT") (pin "3") (pinfunction "3_3") (pintype "passive"))
      (node (ref "LS_BH_R") (pin "18") (pinfunction "B2_18") (pintype "bidirectional"))
    )
    (net (code "30") (name "BH_R_PWM_3V") (class "Default")
      (node (ref "LS_BH_R") (pin "3") (pinfunction "A2_3") (pintype "bidirectional"))
      (node (ref "P8") (pin "13") (pinfunction "13_13") (pintype "passive"))
    )
    (net (code "31") (name "CAN0_RX") (class "Default")
      (node (ref "LS_BH_R") (pin "8") (pinfunction "A7_8") (pintype "bidirectional"))
      (node (ref "P9") (pin "19") (pinfunction "19_19") (pintype "passive"))
    )
    (net (code "32") (name "CAN0_TX") (class "Default")
      (node (ref "LS_BH_R") (pin "7") (pinfunction "A6_7") (pintype "bidirectional"))
      (node (ref "P9") (pin "20") (pinfunction "20_20") (pintype "passive"))
    )
    (net (code "33") (name "CANH") (class "Default")
      (node (ref "CAN") (pin "2") (pinfunction "2_2") (pintype "passive"))
      (node (ref "SJ2") (pin "2") (pinfunction "2_2") (pintype "passive"))
      (node (ref "U$1") (pin "7") (pinfunction "CANH_7") (pintype "bidirectional"))
    )
    (net (code "34") (name "CANL") (class "Default")
      (node (ref "CAN") (pin "3") (pinfunction "3_3") (pintype "passive"))
      (node (ref "R2") (pin "2") (pinfunction "2_2") (pintype "passive"))
      (node (ref "U$1") (pin "6") (pinfunction "CANL_6") (pintype "bidirectional"))
    )
    (net (code "35") (name "CAN_RX") (class "Default")
      (node (ref "LS_BH_R") (pin "13") (pinfunction "B7_13") (pintype "bidirectional"))
      (node (ref "U$1") (pin "4") (pinfunction "RXD_4") (pintype "output"))
    )
    (net (code "36") (name "CAN_TX") (class "Default")
      (node (ref "LS_BH_R") (pin "14") (pinfunction "B6_14") (pintype "bidirectional"))
      (node (ref "U$1") (pin "1") (pinfunction "TXD_1") (pintype "input"))
    )
    (net (code "37") (name "GND") (class "Default")
      (node (ref "9AXIS-IMU") (pin "3") (pinfunction "3_3") (pintype "passive"))
      (node (ref "BALL-HANDLE_LEFT") (pin "1") (pinfunction "1_1") (pintype "passive"))
      (node (ref "BALL-HANDLE_RIGHT") (pin "1") (pinfunction "1_1") (pintype "passive"))
      (node (ref "C1") (pin "2") (pinfunction "2_2") (pintype "passive"))
      (node (ref "C10") (pin "2") (pinfunction "2_2") (pintype "passive"))
      (node (ref "C11") (pin "2") (pinfunction "2_2") (pintype "passive"))
      (node (ref "C12") (pin "2") (pinfunction "2_2") (pintype "passive"))
      (node (ref "C2") (pin "2") (pinfunction "2_2") (pintype "passive"))
      (node (ref "C3") (pin "2") (pinfunction "2_2") (pintype "passive"))
      (node (ref "C4") (pin "2") (pinfunction "2_2") (pintype "passive"))
      (node (ref "C5") (pin "2") (pinfunction "2_2") (pintype "passive"))
      (node (ref "C6") (pin "2") (pinfunction "2_2") (pintype "passive"))
      (node (ref "C7") (pin "2") (pinfunction "2_2") (pintype "passive"))
      (node (ref "C8") (pin "2") (pinfunction "2_2") (pintype "passive"))
      (node (ref "C9") (pin "2") (pinfunction "2_2") (pintype "passive"))
      (node (ref "CAN") (pin "1") (pinfunction "1_1") (pintype "passive"))
      (node (ref "IC1") (pin "4") (pinfunction "GND_4") (pintype "passive"))
      (node (ref "IC2") (pin "4") (pinfunction "GND_4") (pintype "passive"))
      (node (ref "JST_LIGHTBARRIER") (pin "2") (pinfunction "2_2") (pintype "bidirectional"))
      (node (ref "JST_OPTICAL-FLOW") (pin "1") (pinfunction "1_1") (pintype "bidirectional"))
      (node (ref "JST_POTI1") (pin "2") (pinfunction "2_2") (pintype "bidirectional"))
      (node (ref "JST_POTI2") (pin "2") (pinfunction "2_2") (pintype "bidirectional"))
      (node (ref "JST_POTI3") (pin "2") (pinfunction "2_2") (pintype "bidirectional"))
      (node (ref "JST_SERVO") (pin "2") (pinfunction "2_2") (pintype "bidirectional"))
      (node (ref "JST_SERVO2") (pin "2") (pinfunction "2_2") (pintype "bidirectional"))
      (node (ref "JST_SERVO3") (pin "2") (pinfunction "2_2") (pintype "bidirectional"))
      (node (ref "LS_BH_L") (pin "11") (pinfunction "GND_11") (pintype "passive"))
      (node (ref "LS_BH_R") (pin "11") (pinfunction "GND_11") (pintype "passive"))
      (node (ref "LS_IO") (pin "11") (pinfunction "GND_11") (pintype "passive"))
      (node (ref "LS_OF") (pin "11") (pinfunction "GND_11") (pintype "passive"))
      (node (ref "NPN1") (pin "E") (pinfunction "E_E") (pintype "passive"))
      (node (ref "NPN2") (pin "E") (pinfunction "E_E") (pintype "passive"))
      (node (ref "NPN3") (pin "E") (pinfunction "E_E") (pintype "passive"))
      (node (ref "P8") (pin "1") (pinfunction "1_1") (pintype "passive"))
      (node (ref "P8") (pin "2") (pinfunction "2_2") (pintype "passive"))
      (node (ref "P9") (pin "1") (pinfunction "1_1") (pintype "passive"))
      (node (ref "P9") (pin "2") (pinfunction "2_2") (pintype "passive"))
      (node (ref "P9") (pin "34") (pinfunction "34_34") (pintype "passive"))
      (node (ref "P9") (pin "43") (pinfunction "43_43") (pintype "passive"))
      (node (ref "P9") (pin "44") (pinfunction "44_44") (pintype "passive"))
      (node (ref "P9") (pin "45") (pinfunction "45_45") (pintype "passive"))
      (node (ref "P9") (pin "46") (pinfunction "46_46") (pintype "passive"))
      (node (ref "POWER") (pin "2") (pinfunction "2_2") (pintype "bidirectional"))
      (node (ref "R1") (pin "1") (pinfunction "1_1") (pintype "passive"))
      (node (ref "R16") (pin "1") (pinfunction "1_1") (pintype "passive"))
      (node (ref "R17") (pin "1") (pinfunction "1_1") (pintype "passive"))
      (node (ref "R18") (pin "1") (pinfunction "1_1") (pintype "passive"))
      (node (ref "R19") (pin "1") (pinfunction "1_1") (pintype "passive"))
      (node (ref "R20") (pin "1") (pinfunction "1_1") (pintype "passive"))
      (node (ref "R21") (pin "1") (pinfunction "1_1") (pintype "passive"))
      (node (ref "R22") (pin "1") (pinfunction "1_1") (pintype "passive"))
      (node (ref "R3") (pin "1") (pinfunction "1_1") (pintype "passive"))
      (node (ref "R4") (pin "1") (pinfunction "1_1") (pintype "passive"))
      (node (ref "R5") (pin "1") (pinfunction "1_1") (pintype "passive"))
      (node (ref "R6") (pin "1") (pinfunction "1_1") (pintype "passive"))
      (node (ref "SPI_EXTERN") (pin "6") (pinfunction "6_6") (pintype "passive"))
      (node (ref "STECKER_BOX") (pin "1") (pinfunction "1_1") (pintype "passive"))
      (node (ref "STECKER_BOX") (pin "2") (pinfunction "2_2") (pintype "passive"))
      (node (ref "U$1") (pin "2") (pinfunction "VSS_2") (pintype "passive"))
      (node (ref "U1") (pin "2") (pinfunction "GND_2_2") (pintype "passive"))
      (node (ref "U1") (pin "4") (pinfunction "GND_4") (pintype "passive"))
      (node (ref "X1") (pin "2") (pinfunction "KL_2") (pintype "passive"))
    )
    (net (code "38") (name "I2C1_SCL") (class "Default")
      (node (ref "P9") (pin "17") (pinfunction "17_17") (pintype "passive"))
      (node (ref "R29") (pin "1") (pinfunction "1_1") (pintype "passive"))
    )
    (net (code "39") (name "I2C1_SDA") (class "Default")
      (node (ref "P9") (pin "18") (pinfunction "18_18") (pintype "passive"))
      (node (ref "R30") (pin "1") (pinfunction "1_1") (pintype "passive"))
    )
    (net (code "40") (name "IO1") (class "Default")
      (node (ref "IO_EXTERN") (pin "1") (pinfunction "1_1") (pintype "passive"))
      (node (ref "LS_IO") (pin "20") (pinfunction "B1_20") (pintype "bidirectional"))
    )
    (net (code "41") (name "IO1_3V") (class "Default")
      (node (ref "LS_IO") (pin "1") (pinfunction "A1_1") (pintype "bidirectional"))
      (node (ref "P8") (pin "26") (pinfunction "26_26") (pintype "passive"))
    )
    (net (code "42") (name "IO2") (class "Default")
      (node (ref "IO_EXTERN") (pin "2") (pinfunction "2_2") (pintype "passive"))
      (node (ref "LS_IO") (pin "18") (pinfunction "B2_18") (pintype "bidirectional"))
    )
    (net (code "43") (name "IO2_3V") (class "Default")
      (node (ref "LS_IO") (pin "3") (pinfunction "A2_3") (pintype "bidirectional"))
      (node (ref "P8") (pin "27") (pinfunction "27_27") (pintype "passive"))
    )
    (net (code "44") (name "IO3") (class "Default")
      (node (ref "IO_EXTERN") (pin "3") (pinfunction "3_3") (pintype "passive"))
      (node (ref "LS_IO") (pin "17") (pinfunction "B3_17") (pintype "bidirectional"))
    )
    (net (code "45") (name "IO3_3V") (class "Default")
      (node (ref "LS_IO") (pin "4") (pinfunction "A3_4") (pintype "bidirectional"))
      (node (ref "P8") (pin "28") (pinfunction "28_28") (pintype "passive"))
    )
    (net (code "46") (name "IO4") (class "Default")
      (node (ref "IO_EXTERN") (pin "4") (pinfunction "4_4") (pintype "passive"))
      (node (ref "LS_IO") (pin "16") (pinfunction "B4_16") (pintype "bidirectional"))
    )
    (net (code "47") (name "IO4_3V") (class "Default")
      (node (ref "LS_IO") (pin "5") (pinfunction "A4_5") (pintype "bidirectional"))
      (node (ref "P8") (pin "29") (pinfunction "29_29") (pintype "passive"))
    )
    (net (code "48") (name "IO5") (class "Default")
      (node (ref "IO_EXTERN") (pin "5") (pinfunction "5_5") (pintype "passive"))
      (node (ref "LS_IO") (pin "15") (pinfunction "B5_15") (pintype "bidirectional"))
    )
    (net (code "49") (name "IO5_3V") (class "Default")
      (node (ref "LS_IO") (pin "6") (pinfunction "A5_6") (pintype "bidirectional"))
      (node (ref "P8") (pin "30") (pinfunction "30_30") (pintype "passive"))
    )
    (net (code "50") (name "LB_ADC") (class "Default")
      (node (ref "JST_LIGHTBARRIER") (pin "3") (pinfunction "3_3") (pintype "bidirectional"))
      (node (ref "R24") (pin "2") (pinfunction "2_2") (pintype "passive"))
    )
    (net (code "51") (name "LB_ADC_1.8V") (class "Default")
      (node (ref "P9") (pin "40") (pinfunction "40_40") (pintype "passive"))
      (node (ref "R20") (pin "2") (pinfunction "2_2") (pintype "passive"))
      (node (ref "R24") (pin "1") (pinfunction "1_1") (pintype "passive"))
    )
    (net (code "52") (name "LS_BH_L_OE") (class "Default")
      (node (ref "LS_BH_L") (pin "10") (pinfunction "OE_10") (pintype "input"))
      (node (ref "R5") (pin "2") (pinfunction "2_2") (pintype "passive"))
    )
    (net (code "53") (name "LS_BH_R_OE") (class "Default")
      (node (ref "LS_BH_R") (pin "10") (pinfunction "OE_10") (pintype "input"))
      (node (ref "R4") (pin "2") (pinfunction "2_2") (pintype "passive"))
    )
    (net (code "54") (name "LS_IO_OE") (class "Default")
      (node (ref "LS_IO") (pin "10") (pinfunction "OE_10") (pintype "input"))
      (node (ref "R6") (pin "2") (pinfunction "2_2") (pintype "passive"))
    )
    (net (code "55") (name "LS_OF_OE") (class "Default")
      (node (ref "LS_OF") (pin "10") (pinfunction "OE_10") (pintype "input"))
      (node (ref "R3") (pin "2") (pinfunction "2_2") (pintype "passive"))
    )
    (net (code "56") (name "M_DRDY") (class "Default")
      (node (ref "9AXIS-IMU") (pin "6") (pinfunction "6_6") (pintype "passive"))
      (node (ref "P8") (pin "43") (pinfunction "43_43") (pintype "passive"))
    )
    (net (code "57") (name "Net-(9AXIS-IMU-Pad4)") (class "Default")
      (node (ref "9AXIS-IMU") (pin "4") (pinfunction "4_4") (pintype "passive"))
      (node (ref "R27") (pin "1") (pinfunction "1_1") (pintype "passive"))
      (node (ref "R29") (pin "2") (pinfunction "2_2") (pintype "passive"))
    )
    (net (code "58") (name "Net-(9AXIS-IMU-Pad5)") (class "Default")
      (node (ref "9AXIS-IMU") (pin "5") (pinfunction "5_5") (pintype "passive"))
      (node (ref "R28") (pin "1") (pinfunction "1_1") (pintype "passive"))
      (node (ref "R30") (pin "2") (pinfunction "2_2") (pintype "passive"))
    )
    (net (code "59") (name "Net-(CAN-Pad4)") (class "Default")
      (node (ref "CAN") (pin "4") (pinfunction "4_4") (pintype "passive"))
      (node (ref "SJ1") (pin "1") (pinfunction "1_1") (pintype "passive"))
    )
    (net (code "60") (name "Net-(F2-2)") (class "Default")
      (node (ref "F2") (pin "P$2") (pinfunction "2_P$2") (pintype "passive"))
      (node (ref "SJ1") (pin "2") (pinfunction "2_2") (pintype "passive"))
    )
    (net (code "61") (name "Net-(IC1-VI)") (class "Default")
      (node (ref "C1") (pin "1") (pinfunction "1_1") (pintype "passive"))
      (node (ref "C3") (pin "1") (pinfunction "1_1") (pintype "passive"))
      (node (ref "D1") (pin "C") (pinfunction "C_C") (pintype "passive"))
      (node (ref "D2") (pin "C") (pinfunction "C_C") (pintype "passive"))
      (node (ref "F1") (pin "1") (pinfunction "1_1") (pintype "passive"))
      (node (ref "IC1") (pin "1") (pinfunction "VI_1") (pintype "input"))
      (node (ref "IC2") (pin "1") (pinfunction "VI_1") (pintype "input"))
      (node (ref "U1") (pin "1") (pinfunction "IN_1") (pintype "input"))
    )
    (net (code "62") (name "Net-(NPN1-PadC)") (class "Default")
      (node (ref "NPN1") (pin "C") (pinfunction "C_C") (pintype "passive"))
      (node (ref "PNP1") (pin "B") (pinfunction "B_B") (pintype "passive"))
      (node (ref "R13") (pin "1") (pinfunction "1_1") (pintype "passive"))
    )
    (net (code "63") (name "Net-(NPN2-PadC)") (class "Default")
      (node (ref "NPN2") (pin "C") (pinfunction "C_C") (pintype "passive"))
      (node (ref "PNP2") (pin "B") (pinfunction "B_B") (pintype "passive"))
      (node (ref "R14") (pin "1") (pinfunction "1_1") (pintype "passive"))
    )
    (net (code "64") (name "Net-(NPN3-PadC)") (class "Default")
      (node (ref "NPN3") (pin "C") (pinfunction "C_C") (pintype "passive"))
      (node (ref "PNP3") (pin "B") (pinfunction "B_B") (pintype "passive"))
      (node (ref "R15") (pin "1") (pinfunction "1_1") (pintype "passive"))
    )
    (net (code "65") (name "Net-(R2-Pad1)") (class "Default")
      (node (ref "R2") (pin "1") (pinfunction "1_1") (pintype "passive"))
      (node (ref "SJ2") (pin "1") (pinfunction "1_1") (pintype "passive"))
    )
    (net (code "66") (name "Net-(SJ3-Pad2)") (class "Default")
      (node (ref "SJ3") (pin "2") (pinfunction "2_2") (pintype "passive"))
      (node (ref "STECKER_BOX") (pin "9") (pinfunction "9_9") (pintype "passive"))
    )
    (net (code "67") (name "Net-(U$1-RS)") (class "Default")
      (node (ref "R1") (pin "2") (pinfunction "2_2") (pintype "passive"))
      (node (ref "U$1") (pin "8") (pinfunction "RS_8") (pintype "input"))
    )
    (net (code "68") (name "OF_NCS") (class "Default")
      (node (ref "JST_OPTICAL-FLOW") (pin "3") (pinfunction "3_3") (pintype "bidirectional"))
      (node (ref "LS_OF") (pin "14") (pinfunction "B6_14") (pintype "bidirectional"))
    )
    (net (code "69") (name "OF_NCS_3V") (class "Default")
      (node (ref "LS_OF") (pin "7") (pinfunction "A6_7") (pintype "bidirectional"))
      (node (ref "P9") (pin "28") (pinfunction "28_28") (pintype "passive"))
    )
    (net (code "70") (name "OF_NPD") (class "Default")
      (node (ref "JST_OPTICAL-FLOW") (pin "5") (pinfunction "5_5") (pintype "bidirectional"))
      (node (ref "LS_OF") (pin "20") (pinfunction "B1_20") (pintype "bidirectional"))
    )
    (net (code "71") (name "OF_NPD_3V") (class "Default")
      (node (ref "LS_OF") (pin "1") (pinfunction "A1_1") (pintype "bidirectional"))
      (node (ref "P9") (pin "25") (pinfunction "25_25") (pintype "passive"))
    )
    (net (code "72") (name "OF_RST") (class "Default")
      (node (ref "JST_OPTICAL-FLOW") (pin "7") (pinfunction "7_7") (pintype "bidirectional"))
      (node (ref "LS_OF") (pin "18") (pinfunction "B2_18") (pintype "bidirectional"))
    )
    (net (code "73") (name "OF_RST_3V") (class "Default")
      (node (ref "LS_OF") (pin "3") (pinfunction "A2_3") (pintype "bidirectional"))
      (node (ref "P9") (pin "27") (pinfunction "27_27") (pintype "passive"))
    )
    (net (code "74") (name "PWM4") (class "Default")
      (node (ref "IO_EXTERN") (pin "6") (pinfunction "6_6") (pintype "passive"))
      (node (ref "LS_IO") (pin "12") (pinfunction "B8_12") (pintype "bidirectional"))
    )
    (net (code "75") (name "PWM4_3V") (class "Default")
      (node (ref "LS_IO") (pin "9") (pinfunction "A8_9") (pintype "bidirectional"))
      (node (ref "P9") (pin "21") (pinfunction "21_21") (pintype "passive"))
    )
    (net (code "76") (name "P_EOC") (class "Default")
      (node (ref "9AXIS-IMU") (pin "10") (pinfunction "10_10") (pintype "passive"))
      (node (ref "P8") (pin "46") (pinfunction "46_46") (pintype "passive"))
    )
    (net (code "77") (name "P_XCLR") (class "Default")
      (node (ref "9AXIS-IMU") (pin "9") (pinfunction "9_9") (pintype "passive"))
    )
    (net (code "78") (name "SERVO_PWM") (class "Default")
      (node (ref "JST_SERVO") (pin "3") (pinfunction "3_3") (pintype "bidirectional"))
      (node (ref "LS_OF") (pin "13") (pinfunction "B7_13") (pintype "bidirectional"))
    )
    (net (code "79") (name "SERVO_PWM2") (class "Default")
      (node (ref "JST_SERVO2") (pin "3") (pinfunction "3_3") (pintype "bidirectional"))
      (node (ref "LS_IO") (pin "14") (pinfunction "B6_14") (pintype "bidirectional"))
    )
    (net (code "80") (name "SERVO_PWM2_3V") (class "Default")
      (node (ref "LS_IO") (pin "7") (pinfunction "A6_7") (pintype "bidirectional"))
      (node (ref "P9") (pin "16") (pinfunction "16_16") (pintype "passive"))
    )
    (net (code "81") (name "SERVO_PWM3") (class "Default")
      (node (ref "JST_SERVO3") (pin "3") (pinfunction "3_3") (pintype "bidirectional"))
      (node (ref "LS_IO") (pin "13") (pinfunction "B7_13") (pintype "bidirectional"))
    )
    (net (code "82") (name "SERVO_PWM3_3V") (class "Default")
      (node (ref "LS_IO") (pin "8") (pinfunction "A7_8") (pintype "bidirectional"))
      (node (ref "P9") (pin "22") (pinfunction "22_22") (pintype "passive"))
    )
    (net (code "83") (name "SERVO_PWM_3V") (class "Default")
      (node (ref "LS_OF") (pin "8") (pinfunction "A7_8") (pintype "bidirectional"))
      (node (ref "P9") (pin "14") (pinfunction "14_14") (pintype "passive"))
    )
    (net (code "84") (name "SPI1_CLK") (class "Default")
      (node (ref "LS_OF") (pin "4") (pinfunction "A3_4") (pintype "bidirectional"))
      (node (ref "P9") (pin "31") (pinfunction "31_31") (pintype "passive"))
    )
    (net (code "85") (name "SPI1_D0_MISO") (class "Default")
      (node (ref "LS_OF") (pin "5") (pinfunction "A4_5") (pintype "bidirectional"))
      (node (ref "P9") (pin "29") (pinfunction "29_29") (pintype "passive"))
    )
    (net (code "86") (name "SPI1_D1_MOSI") (class "Default")
      (node (ref "LS_OF") (pin "6") (pinfunction "A5_6") (pintype "bidirectional"))
      (node (ref "P9") (pin "30") (pinfunction "30_30") (pintype "passive"))
    )
    (net (code "87") (name "SPI_CLK") (class "Default")
      (node (ref "JST_OPTICAL-FLOW") (pin "6") (pinfunction "6_6") (pintype "bidirectional"))
      (node (ref "LS_OF") (pin "17") (pinfunction "B3_17") (pintype "bidirectional"))
      (node (ref "SPI_EXTERN") (pin "3") (pinfunction "3_3") (pintype "passive"))
    )
    (net (code "88") (name "SPI_CS") (class "Default")
      (node (ref "LS_OF") (pin "12") (pinfunction "B8_12") (pintype "bidirectional"))
      (node (ref "SPI_EXTERN") (pin "5") (pinfunction "5_5") (pintype "passive"))
    )
    (net (code "89") (name "SPI_CS_3V") (class "Default")
      (node (ref "LS_OF") (pin "9") (pinfunction "A8_9") (pintype "bidirectional"))
      (node (ref "P9") (pin "26") (pinfunction "26_26") (pintype "passive"))
    )
    (net (code "90") (name "SPI_MISO") (class "Default")
      (node (ref "JST_OPTICAL-FLOW") (pin "4") (pinfunction "4_4") (pintype "bidirectional"))
      (node (ref "LS_OF") (pin "16") (pinfunction "B4_16") (pintype "bidirectional"))
      (node (ref "SPI_EXTERN") (pin "1") (pinfunction "1_1") (pintype "passive"))
    )
    (net (code "91") (name "SPI_MOSI") (class "Default")
      (node (ref "JST_OPTICAL-FLOW") (pin "2") (pinfunction "2_2") (pintype "bidirectional"))
      (node (ref "LS_OF") (pin "15") (pinfunction "B5_15") (pintype "bidirectional"))
      (node (ref "SPI_EXTERN") (pin "4") (pinfunction "4_4") (pintype "passive"))
    )
    (net (code "92") (name "SW_BUNDLE-LED") (class "Default")
      (node (ref "PNP2") (pin "C") (pinfunction "C_C") (pintype "passive"))
      (node (ref "STECKER_BOX") (pin "8") (pinfunction "8_8") (pintype "passive"))
    )
    (net (code "93") (name "SW_BUNDLE-LED_3V") (class "Default")
      (node (ref "NPN2") (pin "B") (pinfunction "B_B") (pintype "passive"))
      (node (ref "P9") (pin "23") (pinfunction "23_23") (pintype "passive"))
      (node (ref "R17") (pin "2") (pinfunction "2_2") (pintype "passive"))
    )
    (net (code "94") (name "SW_BUNDLE_3V") (class "Default")
      (node (ref "P9") (pin "13") (pinfunction "13_13") (pintype "passive"))
      (node (ref "STECKER_BOX") (pin "7") (pinfunction "7_7") (pintype "passive"))
    )
    (net (code "95") (name "SW_POWER-LED") (class "Default")
      (node (ref "PNP3") (pin "C") (pinfunction "C_C") (pintype "passive"))
      (node (ref "STECKER_BOX") (pin "10") (pinfunction "10_10") (pintype "passive"))
    )
    (net (code "96") (name "SW_POWER-LED_3V") (class "Default")
      (node (ref "NPN3") (pin "B") (pinfunction "B_B") (pintype "passive"))
      (node (ref "P9") (pin "24") (pinfunction "24_24") (pintype "passive"))
      (node (ref "R16") (pin "2") (pinfunction "2_2") (pintype "passive"))
    )
    (net (code "97") (name "SW_POWER_3V") (class "Default")
      (node (ref "P9") (pin "12") (pinfunction "12_12") (pintype "passive"))
      (node (ref "SJ3") (pin "1") (pinfunction "1_1") (pintype "passive"))
    )
    (net (code "98") (name "SW_PWR_BUT") (class "Default")
      (node (ref "P9") (pin "9") (pinfunction "9_9") (pintype "passive"))
      (node (ref "SJ3") (pin "3") (pinfunction "3_3") (pintype "passive"))
    )
    (net (code "99") (name "SW_VISION-LED") (class "Default")
      (node (ref "PNP1") (pin "C") (pinfunction "C_C") (pintype "passive"))
      (node (ref "STECKER_BOX") (pin "6") (pinfunction "6_6") (pintype "passive"))
    )
    (net (code "100") (name "SW_VISION-LED_3V") (class "Default")
      (node (ref "NPN1") (pin "B") (pinfunction "B_B") (pintype "passive"))
      (node (ref "P9") (pin "15") (pinfunction "15_15") (pintype "passive"))
      (node (ref "R18") (pin "2") (pinfunction "2_2") (pintype "passive"))
    )
    (net (code "101") (name "SW_VISION_3V") (class "Default")
      (node (ref "P9") (pin "11") (pinfunction "11_11") (pintype "passive"))
      (node (ref "STECKER_BOX") (pin "5") (pinfunction "5_5") (pintype "passive"))
    )
    (net (code "102") (name "T_INT1") (class "Default")
      (node (ref "9AXIS-IMU") (pin "8") (pinfunction "8_8") (pintype "passive"))
      (node (ref "P8") (pin "45") (pinfunction "45_45") (pintype "passive"))
    )
    (net (code "103") (name "VADC") (class "Default")
      (node (ref "P9") (pin "32") (pinfunction "32_32") (pintype "passive"))
    )
    (net (code "104") (name "unconnected-(9AXIS-IMU-Pad1)") (class "Default")
      (node (ref "9AXIS-IMU") (pin "1") (pinfunction "1_1") (pintype "passive"))
    )
    (net (code "105") (name "unconnected-(BALL-HANDLE_LEFT-Pad7)") (class "Default")
      (node (ref "BALL-HANDLE_LEFT") (pin "7") (pinfunction "7_7") (pintype "passive"))
    )
    (net (code "106") (name "unconnected-(BALL-HANDLE_LEFT-Pad8)") (class "Default")
      (node (ref "BALL-HANDLE_LEFT") (pin "8") (pinfunction "8_8") (pintype "passive"))
    )
    (net (code "107") (name "unconnected-(BALL-HANDLE_RIGHT-Pad7)") (class "Default")
      (node (ref "BALL-HANDLE_RIGHT") (pin "7") (pinfunction "7_7") (pintype "passive"))
    )
    (net (code "108") (name "unconnected-(BALL-HANDLE_RIGHT-Pad8)") (class "Default")
      (node (ref "BALL-HANDLE_RIGHT") (pin "8") (pinfunction "8_8") (pintype "passive"))
    )
    (net (code "109") (name "unconnected-(LS_BH_L-A1-Pad1)") (class "Default")
      (node (ref "LS_BH_L") (pin "1") (pinfunction "A1_1") (pintype "bidirectional"))
    )
    (net (code "110") (name "unconnected-(LS_BH_L-A2-Pad3)") (class "Default")
      (node (ref "LS_BH_L") (pin "3") (pinfunction "A2_3") (pintype "bidirectional"))
    )
    (net (code "111") (name "unconnected-(LS_BH_L-A3-Pad4)") (class "Default")
      (node (ref "LS_BH_L") (pin "4") (pinfunction "A3_4") (pintype "bidirectional"))
    )
    (net (code "112") (name "unconnected-(LS_BH_L-B1-Pad20)") (class "Default")
      (node (ref "LS_BH_L") (pin "20") (pinfunction "B1_20") (pintype "bidirectional"))
    )
    (net (code "113") (name "unconnected-(LS_BH_L-B2-Pad18)") (class "Default")
      (node (ref "LS_BH_L") (pin "18") (pinfunction "B2_18") (pintype "bidirectional"))
    )
    (net (code "114") (name "unconnected-(LS_BH_L-B3-Pad17)") (class "Default")
      (node (ref "LS_BH_L") (pin "17") (pinfunction "B3_17") (pintype "bidirectional"))
    )
    (net (code "115") (name "unconnected-(LS_BH_R-A8-Pad9)") (class "Default")
      (node (ref "LS_BH_R") (pin "9") (pinfunction "A8_9") (pintype "bidirectional"))
    )
    (net (code "116") (name "unconnected-(LS_BH_R-B8-Pad12)") (class "Default")
      (node (ref "LS_BH_R") (pin "12") (pinfunction "B8_12") (pintype "bidirectional"))
    )
    (net (code "117") (name "unconnected-(P8-Pad3)") (class "Default")
      (node (ref "P8") (pin "3") (pinfunction "3_3") (pintype "passive"))
    )
    (net (code "118") (name "unconnected-(P8-Pad4)") (class "Default")
      (node (ref "P8") (pin "4") (pinfunction "4_4") (pintype "passive"))
    )
    (net (code "119") (name "unconnected-(P8-Pad5)") (class "Default")
      (node (ref "P8") (pin "5") (pinfunction "5_5") (pintype "passive"))
    )
    (net (code "120") (name "unconnected-(P8-Pad6)") (class "Default")
      (node (ref "P8") (pin "6") (pinfunction "6_6") (pintype "passive"))
    )
    (net (code "121") (name "unconnected-(P8-Pad7)") (class "Default")
      (node (ref "P8") (pin "7") (pinfunction "7_7") (pintype "passive"))
    )
    (net (code "122") (name "unconnected-(P8-Pad8)") (class "Default")
      (node (ref "P8") (pin "8") (pinfunction "8_8") (pintype "passive"))
    )
    (net (code "123") (name "unconnected-(P8-Pad9)") (class "Default")
      (node (ref "P8") (pin "9") (pinfunction "9_9") (pintype "passive"))
    )
    (net (code "124") (name "unconnected-(P8-Pad10)") (class "Default")
      (node (ref "P8") (pin "10") (pinfunction "10_10") (pintype "passive"))
    )
    (net (code "125") (name "unconnected-(P8-Pad11)") (class "Default")
      (node (ref "P8") (pin "11") (pinfunction "11_11") (pintype "passive"))
    )
    (net (code "126") (name "unconnected-(P8-Pad12)") (class "Default")
      (node (ref "P8") (pin "12") (pinfunction "12_12") (pintype "passive"))
    )
    (net (code "127") (name "unconnected-(P8-Pad14)") (class "Default")
      (node (ref "P8") (pin "14") (pinfunction "14_14") (pintype "passive"))
    )
    (net (code "128") (name "unconnected-(P8-Pad15)") (class "Default")
      (node (ref "P8") (pin "15") (pinfunction "15_15") (pintype "passive"))
    )
    (net (code "129") (name "unconnected-(P8-Pad16)") (class "Default")
      (node (ref "P8") (pin "16") (pinfunction "16_16") (pintype "passive"))
    )
    (net (code "130") (name "unconnected-(P8-Pad17)") (class "Default")
      (node (ref "P8") (pin "17") (pinfunction "17_17") (pintype "passive"))
    )
    (net (code "131") (name "unconnected-(P8-Pad18)") (class "Default")
      (node (ref "P8") (pin "18") (pinfunction "18_18") (pintype "passive"))
    )
    (net (code "132") (name "unconnected-(P8-Pad20)") (class "Default")
      (node (ref "P8") (pin "20") (pinfunction "20_20") (pintype "passive"))
    )
    (net (code "133") (name "unconnected-(P8-Pad21)") (class "Default")
      (node (ref "P8") (pin "21") (pinfunction "21_21") (pintype "passive"))
    )
    (net (code "134") (name "unconnected-(P8-Pad22)") (class "Default")
      (node (ref "P8") (pin "22") (pinfunction "22_22") (pintype "passive"))
    )
    (net (code "135") (name "unconnected-(P8-Pad23)") (class "Default")
      (node (ref "P8") (pin "23") (pinfunction "23_23") (pintype "passive"))
    )
    (net (code "136") (name "unconnected-(P8-Pad24)") (class "Default")
      (node (ref "P8") (pin "24") (pinfunction "24_24") (pintype "passive"))
    )
    (net (code "137") (name "unconnected-(P8-Pad25)") (class "Default")
      (node (ref "P8") (pin "25") (pinfunction "25_25") (pintype "passive"))
    )
    (net (code "138") (name "unconnected-(P8-Pad31)") (class "Default")
      (node (ref "P8") (pin "31") (pinfunction "31_31") (pintype "passive"))
    )
    (net (code "139") (name "unconnected-(P8-Pad32)") (class "Default")
      (node (ref "P8") (pin "32") (pinfunction "32_32") (pintype "passive"))
    )
    (net (code "140") (name "unconnected-(P8-Pad33)") (class "Default")
      (node (ref "P8") (pin "33") (pinfunction "33_33") (pintype "passive"))
    )
    (net (code "141") (name "unconnected-(P8-Pad35)") (class "Default")
      (node (ref "P8") (pin "35") (pinfunction "35_35") (pintype "passive"))
    )
    (net (code "142") (name "unconnected-(P9-Pad7)") (class "Default")
      (node (ref "P9") (pin "7") (pinfunction "7_7") (pintype "passive"))
    )
    (net (code "143") (name "unconnected-(P9-Pad8)") (class "Default")
      (node (ref "P9") (pin "8") (pinfunction "8_8") (pintype "passive"))
    )
    (net (code "144") (name "unconnected-(P9-Pad41)") (class "Default")
      (node (ref "P9") (pin "41") (pinfunction "41_41") (pintype "passive"))
    )
    (net (code "145") (name "unconnected-(P9-Pad42)") (class "Default")
      (node (ref "P9") (pin "42") (pinfunction "42_42") (pintype "passive"))
    )
    (net (code "146") (name "unconnected-(STECKER_BOX-Pad3)") (class "Default")
      (node (ref "STECKER_BOX") (pin "3") (pinfunction "3_3") (pintype "passive"))
    )
    (net (code "147") (name "unconnected-(STECKER_BOX-Pad4)") (class "Default")
      (node (ref "STECKER_BOX") (pin "4") (pinfunction "4_4") (pintype "passive"))
    )
    (net (code "148") (name "unconnected-(U$1-VREF-Pad5)") (class "Default")
      (node (ref "U$1") (pin "5") (pinfunction "VREF_5") (pintype "output"))
    )
    (net (code "149") (name "~{BH_L_RESET_3V}") (class "Default")
      (node (ref "LS_BH_L") (pin "7") (pinfunction "A6_7") (pintype "bidirectional"))
      (node (ref "P8") (pin "39") (pinfunction "39_39") (pintype "passive"))
    )
    (net (code "150") (name "~{BH_L_RESET}") (class "Default")
      (node (ref "BALL-HANDLE_LEFT") (pin "4") (pinfunction "4_4") (pintype "passive"))
      (node (ref "LS_BH_L") (pin "14") (pinfunction "B6_14") (pintype "bidirectional"))
    )
    (net (code "151") (name "~{BH_R_RESET_3V}") (class "Default")
      (node (ref "LS_BH_R") (pin "4") (pinfunction "A3_4") (pintype "bidirectional"))
      (node (ref "P8") (pin "34") (pinfunction "34_34") (pintype "passive"))
    )
    (net (code "152") (name "~{BH_R_RESET}") (class "Default")
      (node (ref "BALL-HANDLE_RIGHT") (pin "4") (pinfunction "4_4") (pintype "passive"))
      (node (ref "LS_BH_R") (pin "17") (pinfunction "B3_17") (pintype "bidirectional"))
    )
    (net (code "153") (name "~{SYS_RESET}") (class "Default")
      (node (ref "P9") (pin "10") (pinfunction "10_10") (pintype "passive"))
    )
  )
)
